# J1962_Connector.net
KiCad netlist of a schematic drawn in Altium Designer
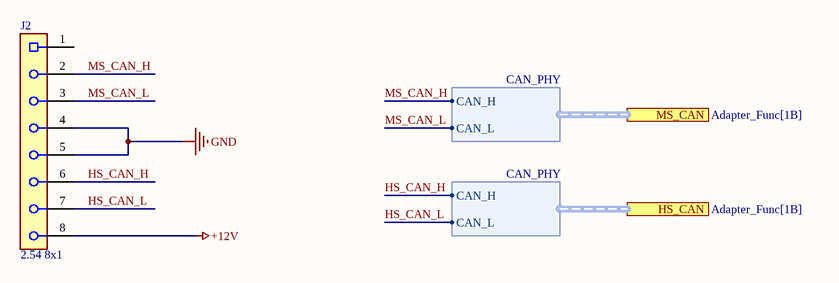
[diagram p0: J1962 Connector.SchDoc]

(export (version "E")
  (design (tool "Eeschema 10.0.6"))
  (components
    (comp (ref "J2") (value "2.54 8x1") (footprint "PLS-8X1") (libsource (lib "Max_lib") (part "2.54mm 8x1")))
  )
  (nets
    (net (code "2") (name "+12V") (class "Default")
      (node (ref "J2") (pin "8") (pinfunction "8_8") (pintype "passive"))
    )
    (net (code "3") (name "/HS_CAN_H") (class "Default")
      (node (ref "J2") (pin "6") (pinfunction "6_6") (pintype "passive"))
    )
    (net (code "4") (name "/HS_CAN_L") (class "Default")
      (node (ref "J2") (pin "7") (pinfunction "7_7") (pintype "passive"))
    )
    (net (code "5") (name "/MS_CAN_H") (class "Default")
      (node (ref "J2") (pin "2") (pinfunction "2_2") (pintype "passive"))
    )
    (net (code "6") (name "/MS_CAN_L") (class "Default")
      (node (ref "J2") (pin "3") (pinfunction "3_3") (pintype "passive"))
    )
    (net (code "8") (name "GND") (class "Default")
      (node (ref "J2") (pin "4") (pinfunction "4_4") (pintype "passive"))
      (node (ref "J2") (pin "5") (pinfunction "5_5") (pintype "passive"))
    )
    (net (code "9") (name "unconnected-(J2-Pad1)") (class "Default")
      (node (ref "J2") (pin "1") (pinfunction "1_1") (pintype "passive"))
    )
  )
)
